# High-Efficiency_3_3V_DC-DC_Converter_for.net
KiCad netlist of a schematic drawn in Altium Designer
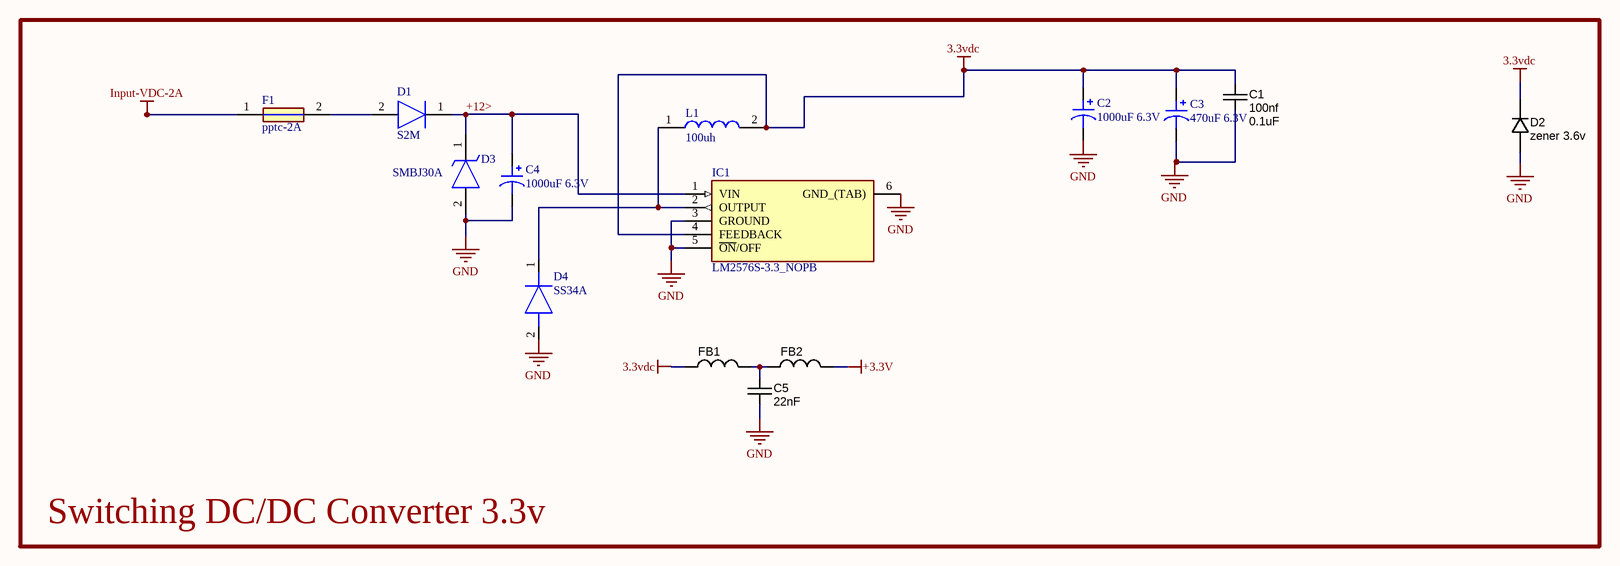
[diagram p0: High-Efficiency 3.3V DC-DC Converter for STM32.SchDoc]

(export (version "E")
  (design (tool "Eeschema 10.0.6"))
  (components
    (comp (ref "C1")
      (value "100nf")
      (footprint "CAPC3316X185N")
      (description "Capacitor SMD Cer 100n 10% 50V X7R 0805")
      (fields (field (name "TOLERANCE") "±10%") (field (name "ALTIUM_VALUE") "0.1uF"))
      (libsource (lib "PBL - Capacitors") (part "CAPC_1n8_50V_0805"))
    )
    (comp (ref "C2")
      (value "1000uF 6.3V")
      (footprint "CAP ALSMD POLY 8.3MM H9.0MM")
      (description "SMT Aluminum Polymer Capacitor")
      (libsource (lib "Capacitor") (part "Cap Alu SMD 8.3mm H9.0mm"))
    )
    (comp (ref "C3")
      (value "470uF 6.3V")
      (footprint "CAP ALSMD POLY 6.3MM H5.8MM")
      (description "470uf")
      (libsource (lib "Capacitor") (part "Cap Alu SMD 6.3mm H5.8mm"))
    )
    (comp (ref "C4")
      (value "1000uF 6.3V")
      (footprint "CAP ALSMD POLY 8.3MM H9.0MM")
      (description "SMT Aluminum Polymer Capacitor")
      (libsource (lib "Capacitor") (part "Cap Alu SMD 8.3mm H9.0mm"))
    )
    (comp (ref "C5")
      (value "22nF")
      (footprint "CAPC3216X180N")
      (description "Capacitor SMD Cer 1uF 10% 16V X7R 0805")
      (fields (field (name "TOLERANCE") "±10%") (field (name "Comment") "22nf_0805"))
      (libsource (lib "PBL - Capacitors") (part "CAPC_1u_0805_X7R_16V_10%"))
    )
    (comp (ref "D1")
      (value "S2M")
      (footprint "SamacSys:DIOM5336X265N")
      (description "Diode")
      (fields (field (name "MOUSER PART NUMBER") "512-S2M"))
      (libsource (lib "*") (part "S2M"))
    )
    (comp (ref "D2")
      (value "Mini MELF")
      (footprint "SOD80, LL-34")
      (description "Diode SMD 3.6v 150mA 500mW SOD80")
      (fields (field (name "MANUFACTURER PART NUMBER 1") "zener 3.6v"))
      (libsource (lib "PBL - Diodes") (part "DIODE_100V_500mW_MELF"))
    )
    (comp (ref "D3")
      (value "SMBJ30A")
      (footprint "DIOM5436X261N")
      (fields (field (name "MOUSER PART NUMBER") "576-SMBJ30A"))
      (libsource (lib "*") (part "SMBJ30A"))
    )
    (comp (ref "D4")
      (value "SS34A")
      (footprint "SamacSys:DIOM5026X262N")
      (description "Diode")
      (libsource (lib "SamacSys") (part "SS34A"))
    )
    (comp (ref "F1")
      (value "pptc-2A")
      (footprint "FUSC3216X75N")
      (description "pptc 500ma")
      (fields
        (field (name "MANUFACTURER_PART_NUMBER") "0805L050WR")
        (field (name "MOUSER PART NUMBER") "576-0805L050")
      )
      (libsource (lib "SamacSys") (part "0805L050WR"))
    )
    (comp (ref "FB1")
      (value "fb_1K@100MHZ_0805")
      (footprint "FUSC3216X75N")
      (libsource (lib "PBL - Inductors") (part "FERRITE_2K2-100MHz_0805"))
    )
    (comp (ref "FB2")
      (value "fb_1K@100MHZ_0805")
      (footprint "FUSC3216X75N")
      (libsource (lib "PBL - Inductors") (part "FERRITE_2K2-100MHz_0805"))
    )
    (comp (ref "IC1")
      (value "LM2576S-3.3_NOPB")
      (footprint "SamacSys:TO170P1435X465-6N")
      (description "Integrated Circuit")
      (fields
        (field (name "MANUFACTURER_PART_NUMBER") "LM2576S-3.3/NOPB")
        (field (name "MOUSER PART NUMBER") "926-LM2576S-3.3/NOPB")
      )
      (libsource (lib "SamacSys") (part "LM2576S-3.3_NOPB"))
    )
    (comp (ref "L1")
      (value "100uh")
      (footprint "SamacSys:CD75NP221KC")
      (fields
        (field (name "MANUFACTURER_PART_NUMBER") "SRN8040-101M")
        (field (name "MOUSER PART NUMBER") "652-SRN8040-101M")
      )
      (libsource (lib "SamacSys") (part "SRN8040-101M"))
    )
  )
  (nets
    (net (code "1") (name "+3.3V") (class "Default")
      (node (ref "FB2") (pin "2") (pinfunction "2_2") (pintype "passive"))
    )
    (net (code "2") (name "/+12>") (class "Default")
      (node (ref "C4") (pin "1") (pinfunction "1_1") (pintype "passive"))
      (node (ref "D1") (pin "1") (pinfunction "K_1") (pintype "passive"))
      (node (ref "D3") (pin "1") (pinfunction "K_1") (pintype "passive"))
      (node (ref "IC1") (pin "1") (pinfunction "VIN_1") (pintype "input"))
    )
    (net (code "3") (name "3.3vdc") (class "Default")
      (node (ref "C1") (pin "1") (pintype "passive"))
      (node (ref "C2") (pin "1") (pinfunction "1_1") (pintype "passive"))
      (node (ref "C3") (pin "1") (pinfunction "1_1") (pintype "passive"))
      (node (ref "D2") (pin "K") (pinfunction "K_K") (pintype "passive"))
      (node (ref "FB1") (pin "1") (pinfunction "1_1") (pintype "passive"))
      (node (ref "IC1") (pin "4") (pinfunction "FEEDBACK_4") (pintype "passive"))
      (node (ref "L1") (pin "2") (pinfunction "2_2") (pintype "passive"))
    )
    (net (code "4") (name "GND") (class "Default")
      (node (ref "C1") (pin "2") (pintype "passive"))
      (node (ref "C2") (pin "2") (pinfunction "2_2") (pintype "passive"))
      (node (ref "C3") (pin "2") (pinfunction "2_2") (pintype "passive"))
      (node (ref "C4") (pin "2") (pinfunction "2_2") (pintype "passive"))
      (node (ref "C5") (pin "2") (pintype "passive"))
      (node (ref "D2") (pin "A") (pinfunction "A_A") (pintype "passive"))
      (node (ref "D3") (pin "2") (pinfunction "A_2") (pintype "passive"))
      (node (ref "D4") (pin "2") (pinfunction "A_2") (pintype "passive"))
      (node (ref "IC1") (pin "3") (pinfunction "GROUND_3") (pintype "passive"))
      (node (ref "IC1") (pin "5") (pinfunction "~{ON}/OFF_5") (pintype "passive"))
      (node (ref "IC1") (pin "6") (pinfunction "GND_(TAB)_6") (pintype "power_in"))
    )
    (net (code "5") (name "Input-VDC-2A") (class "Default")
      (node (ref "F1") (pin "1") (pinfunction "1_1") (pintype "passive"))
    )
    (net (code "6") (name "Net-(C5-Pad1)") (class "Default")
      (node (ref "C5") (pin "1") (pintype "passive"))
      (node (ref "FB1") (pin "2") (pinfunction "2_2") (pintype "passive"))
      (node (ref "FB2") (pin "1") (pinfunction "1_1") (pintype "passive"))
    )
    (net (code "7") (name "Net-(D1-A)") (class "Default")
      (node (ref "D1") (pin "2") (pinfunction "A_2") (pintype "passive"))
      (node (ref "F1") (pin "2") (pinfunction "2_2") (pintype "passive"))
    )
    (net (code "8") (name "Net-(D4-K)") (class "Default")
      (node (ref "D4") (pin "1") (pinfunction "K_1") (pintype "passive"))
      (node (ref "IC1") (pin "2") (pinfunction "OUTPUT_2") (pintype "output"))
      (node (ref "L1") (pin "1") (pinfunction "1_1") (pintype "passive"))
    )
  )
)
